# PiZero-RAK.net
KiCad netlist of a schematic drawn in EAGLE
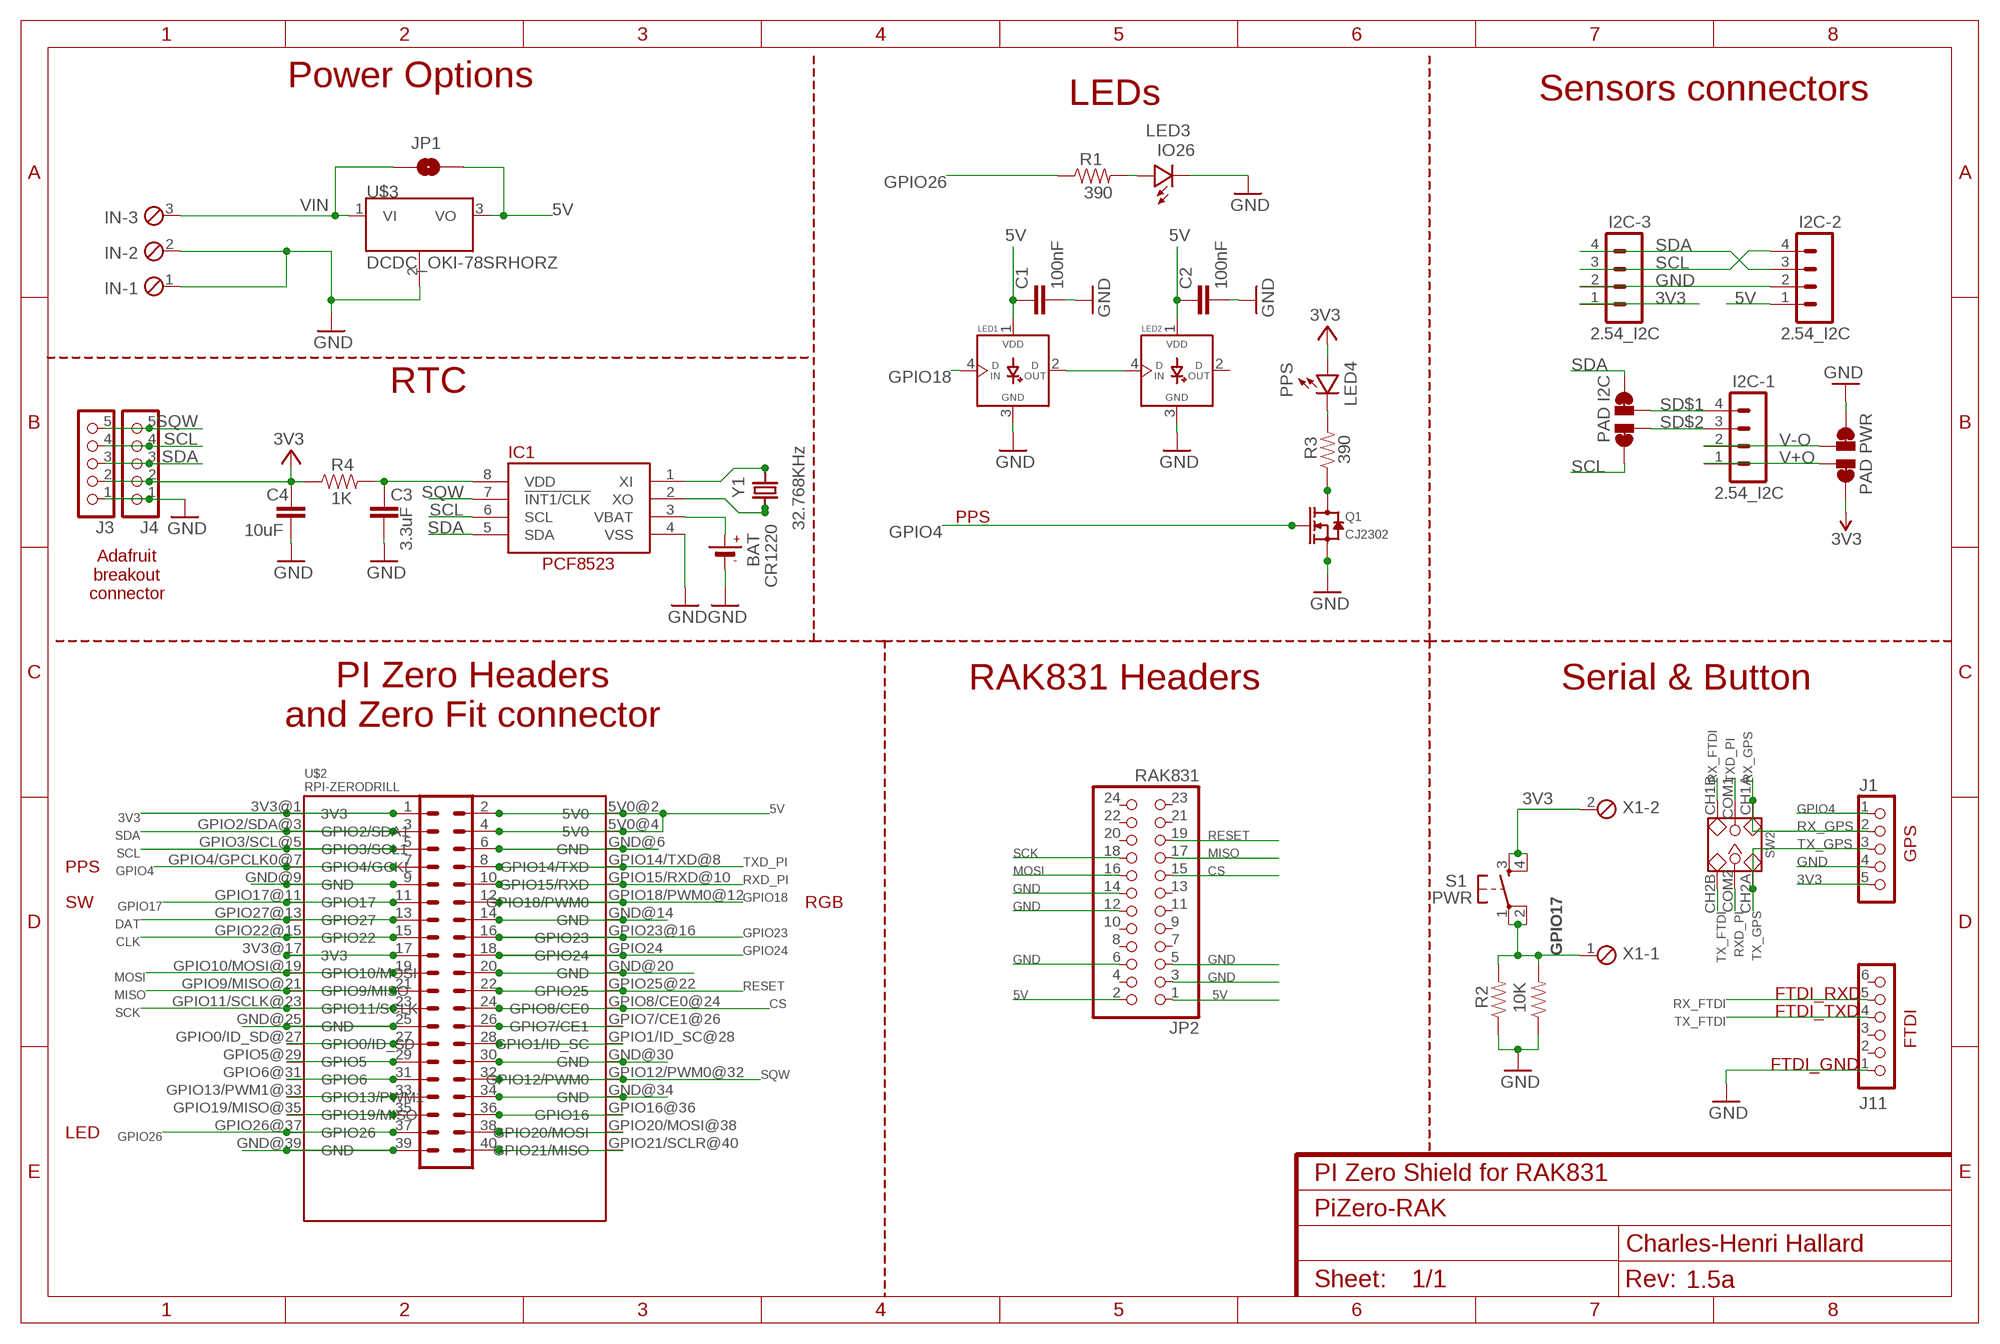
[diagram p0: schematic, sheet 1]

(export (version "E")
  (design (tool "Eeschema 10.0.6"))
  (components
    (comp (ref "BAT")
      (value "CR1220")
      (footprint "eagle-import:CR1220")
      (libsource (lib "eagle-import") (part "BATTERYCR1220_SMT"))
    )
    (comp (ref "C1")
      (value "100nF")
      (footprint "eagle-import:0805-CAP-LARGEPADS")
      (libsource (lib "eagle-import") (part "CAP0805-CAP-LARGEPADS"))
    )
    (comp (ref "C2")
      (value "100nF")
      (footprint "eagle-import:0805-CAP-LARGEPADS")
      (libsource (lib "eagle-import") (part "CAP0805-CAP-LARGEPADS"))
    )
    (comp (ref "C3")
      (value "3.3uF")
      (footprint "eagle-import:0805-CAP-LARGEPADS")
      (libsource (lib "eagle-import") (part "CAP0805-CAP-LARGEPADS"))
    )
    (comp (ref "C4")
      (value "10uF")
      (footprint "eagle-import:0805-CAP-LARGEPADS")
      (libsource (lib "eagle-import") (part "CAP0805-CAP-LARGEPADS"))
    )
    (comp (ref "I2C-1")
      (value "2.54_I2C")
      (footprint "eagle-import:1X04_NO_LOCK")
      (libsource (lib "eagle-import") (part "CON_HEADER_1X04'NO_LOCK'"))
    )
    (comp (ref "I2C-2")
      (value "2.54_I2C")
      (footprint "eagle-import:1X04_NO_LOCK")
      (libsource (lib "eagle-import") (part "CON_HEADER_1X04'NO_LOCK'"))
    )
    (comp (ref "I2C-3")
      (value "2.54_I2C")
      (footprint "eagle-import:1X04_NO_LOCK")
      (libsource (lib "eagle-import") (part "CON_HEADER_1X04'NO_LOCK'"))
    )
    (comp (ref "IC1")
      (value "PCF8523")
      (footprint "eagle-import:SOIC8_150MIL")
      (libsource (lib "eagle-import") (part "RTC_PCF8523T"))
    )
    (comp (ref "IN")
      (value "MPT3")
      (footprint "eagle-import:3POL254")
      (libsource (lib "eagle-import") (part "MPT3"))
    )
    (comp (ref "J1")
      (value "CON_HEADER_1X05-PTH")
      (footprint "eagle-import:M1X5")
      (libsource (lib "eagle-import") (part "CON_HEADER_1X05-PTH"))
    )
    (comp (ref "J2")
      (value "CONN_20X2HLE")
      (footprint "eagle-import:2X20-HLE")
      (libsource (lib "eagle-import") (part "CONN_20X2HLE"))
    )
    (comp (ref "J3")
      (value "CON_HEADER_1X05-PTH")
      (footprint "eagle-import:M1X5")
      (libsource (lib "eagle-import") (part "CON_HEADER_1X05-PTH"))
    )
    (comp (ref "J4")
      (value "CON_HEADER_1X05-PTH")
      (footprint "eagle-import:M1X5")
      (libsource (lib "eagle-import") (part "CON_HEADER_1X05-PTH"))
    )
    (comp (ref "J11")
      (value "CON_HEADER_1X06-PTH")
      (footprint "eagle-import:M1X6")
      (libsource (lib "eagle-import") (part "CON_HEADER_1X06-PTH"))
    )
    (comp (ref "JP1")
      (value "JUMPER-PAD-2-NOYES_SILK")
      (footprint "eagle-import:PAD-JUMPER-2-NO_YES_SILK")
      (libsource (lib "eagle-import") (part "JUMPER-PAD-2-NOYES_SILK"))
    )
    (comp (ref "JP2")
      (value "RAK831")
      (footprint "eagle-import:2X12")
      (libsource (lib "eagle-import") (part "PINHD-2X12"))
    )
    (comp (ref "LED1")
      (value "WS2812BLONG")
      (footprint "eagle-import:WS2812B-LONG")
      (libsource (lib "eagle-import") (part "WS2812BLONG"))
    )
    (comp (ref "LED2")
      (value "WS2812BLONG")
      (footprint "eagle-import:WS2812B-LONG")
      (libsource (lib "eagle-import") (part "WS2812BLONG"))
    )
    (comp (ref "LED3")
      (value "IO26")
      (footprint "eagle-import:0805-LED-LARGEPADS")
      (libsource (lib "eagle-import") (part "LED0805-LARGE"))
    )
    (comp (ref "LED4")
      (value "PPS")
      (footprint "eagle-import:0805-LED-LARGEPADS")
      (libsource (lib "eagle-import") (part "LED0805-LARGE"))
    )
    (comp (ref "Q1")
      (value "CJ2302")
      (footprint "eagle-import:SOT-23")
      (libsource (lib "eagle-import") (part "SMD-MOSFET-N-CH-20V-2.1A-CJ2302(SOT-23)"))
    )
    (comp (ref "R1")
      (value "390")
      (footprint "eagle-import:0805-RES")
      (libsource (lib "eagle-import") (part "RESISTOR0805-RES"))
    )
    (comp (ref "R2")
      (value "10K")
      (footprint "eagle-import:AXIAL-0.3")
      (libsource (lib "eagle-import") (part "RESISTORAXIAL-0.3"))
    )
    (comp (ref "R3")
      (value "390")
      (footprint "eagle-import:0805-RES")
      (libsource (lib "eagle-import") (part "RESISTOR0805-RES"))
    )
    (comp (ref "R4")
      (value "1K")
      (footprint "eagle-import:0805-RES")
      (libsource (lib "eagle-import") (part "RESISTOR0805-RES"))
    )
    (comp (ref "R105")
      (value "RESISTOR0805-RES")
      (footprint "eagle-import:0805-RES")
      (libsource (lib "eagle-import") (part "RESISTOR0805-RES"))
    )
    (comp (ref "S1")
      (value "PWR")
      (footprint "eagle-import:TAC-SWITCH-PTH")
      (libsource (lib "eagle-import") (part "TACTILE-SWITCH-PTH"))
    )
    (comp (ref "SW2")
      (value "DIP-TOGGLE-SWITCH-2CH-(2X3P-2.54)")
      (footprint "eagle-import:SW6-2.54-9.0X3.5X3.2+2.0MM")
      (fields (field (name "MPN") "MS-22D18 G2 ROHS"))
      (libsource (lib "eagle-import") (part "DIP-TOGGLE-SWITCH-2CH-(2X3P-2.54)"))
    )
    (comp (ref "U$2")
      (value "RPI-ZERODRILL")
      (footprint "eagle-import:RPI-ZERO-DRILLS")
      (libsource (lib "eagle-import") (part "RPI-ZERODRILL"))
    )
    (comp (ref "U$3")
      (value "DCDC_OKI-78SRHORZ")
      (footprint "eagle-import:OKI-78SRH")
      (libsource (lib "eagle-import") (part "DCDC_OKI-78SRHORZ"))
    )
    (comp (ref "U$4")
      (value "PAD PWR")
      (footprint "eagle-import:PAD-JUMPER-SWAP")
      (libsource (lib "eagle-import") (part "PAD-JUMPER-SWAPSWAP"))
    )
    (comp (ref "U$5")
      (value "PAD I2C")
      (footprint "eagle-import:PAD-JUMPER-SWAP")
      (libsource (lib "eagle-import") (part "PAD-JUMPER-SWAPSWAP"))
    )
    (comp (ref "X1")
      (value "MPT2")
      (footprint "eagle-import:2POL254")
      (libsource (lib "eagle-import") (part "MPT2"))
    )
    (comp (ref "Y1")
      (value "32.768KHz")
      (footprint "eagle-import:TC26H")
      (libsource (lib "eagle-import") (part "CRYSTALTC26H"))
    )
    (comp (ref "Y2")
      (value "CRYSTAL8X3.8SMT")
      (footprint "eagle-import:CRYSTAL_8X3.8")
      (libsource (lib "eagle-import") (part "CRYSTAL8X3.8SMT"))
    )
  )
  (nets
    (net (code "1") (name "/SD$1") (class "Default")
      (node (ref "I2C-1") (pin "4") (pinfunction "4_4") (pintype "passive"))
      (node (ref "U$5") (pin "3") (pinfunction "3_3") (pintype "passive"))
    )
    (net (code "2") (name "/SD$2") (class "Default")
      (node (ref "I2C-1") (pin "3") (pinfunction "3_3") (pintype "passive"))
      (node (ref "U$5") (pin "2") (pinfunction "2_2") (pintype "passive"))
    )
    (net (code "3") (name "/V+O") (class "Default")
      (node (ref "I2C-1") (pin "1") (pinfunction "1_1") (pintype "passive"))
      (node (ref "U$4") (pin "3") (pinfunction "3_3") (pintype "passive"))
    )
    (net (code "4") (name "/V-O") (class "Default")
      (node (ref "I2C-1") (pin "2") (pinfunction "2_2") (pintype "passive"))
      (node (ref "U$4") (pin "2") (pinfunction "2_2") (pintype "passive"))
    )
    (net (code "5") (name "/VIN") (class "Default")
      (node (ref "IN") (pin "3") (pinfunction "1_3") (pintype "passive"))
      (node (ref "JP1") (pin "1") (pinfunction "1_1") (pintype "passive"))
      (node (ref "U$3") (pin "1") (pinfunction "VI_1") (pintype "bidirectional"))
    )
    (net (code "6") (name "3V3") (class "Default")
      (node (ref "C4") (pin "1") (pinfunction "1_1") (pintype "passive"))
      (node (ref "I2C-3") (pin "1") (pinfunction "1_1") (pintype "passive"))
      (node (ref "J1") (pin "5") (pinfunction "5_5") (pintype "bidirectional"))
      (node (ref "J2") (pin "1") (pinfunction "1_1") (pintype "passive"))
      (node (ref "J3") (pin "2") (pinfunction "2_2") (pintype "bidirectional"))
      (node (ref "J4") (pin "2") (pinfunction "2_2") (pintype "bidirectional"))
      (node (ref "LED4") (pin "PLUS") (pinfunction "PLUS_PLUS") (pintype "passive"))
      (node (ref "R4") (pin "1") (pinfunction "1_1") (pintype "passive"))
      (node (ref "S1") (pin "3") (pinfunction "3_3") (pintype "passive"))
      (node (ref "S1") (pin "4") (pinfunction "4_4") (pintype "passive"))
      (node (ref "U$2") (pin "3V3@1") (pinfunction "3V3_3V3@1") (pintype "power_in"))
      (node (ref "U$4") (pin "4") (pinfunction "4_4") (pintype "passive"))
      (node (ref "U$4") (pin "44") (pinfunction "4_44") (pintype "passive"))
      (node (ref "X1") (pin "2") (pinfunction "1_2") (pintype "passive"))
    )
    (net (code "7") (name "5V") (class "Default")
      (node (ref "C1") (pin "1") (pinfunction "1_1") (pintype "passive"))
      (node (ref "C2") (pin "1") (pinfunction "1_1") (pintype "passive"))
      (node (ref "I2C-2") (pin "1") (pinfunction "1_1") (pintype "passive"))
      (node (ref "J2") (pin "2") (pinfunction "2_2") (pintype "passive"))
      (node (ref "J2") (pin "4") (pinfunction "4_4") (pintype "passive"))
      (node (ref "JP1") (pin "2") (pinfunction "2_2") (pintype "passive"))
      (node (ref "JP2") (pin "1") (pinfunction "1_1") (pintype "passive"))
      (node (ref "JP2") (pin "2") (pinfunction "2_2") (pintype "passive"))
      (node (ref "LED1") (pin "1") (pinfunction "VDD_1") (pintype "power_in"))
      (node (ref "LED2") (pin "1") (pinfunction "VDD_1") (pintype "power_in"))
      (node (ref "U$2") (pin "5V0@2") (pinfunction "5V0_5V0@2") (pintype "power_in"))
      (node (ref "U$2") (pin "5V0@4") (pinfunction "5V0_5V0@4") (pintype "power_in"))
      (node (ref "U$3") (pin "3") (pinfunction "VO_3") (pintype "bidirectional"))
    )
    (net (code "8") (name "CLK") (class "Default")
      (node (ref "J2") (pin "15") (pinfunction "15_15") (pintype "passive"))
      (node (ref "U$2") (pin "GPIO22@15") (pinfunction "GPIO22_GPIO22@15") (pintype "bidirectional"))
    )
    (net (code "9") (name "CS") (class "Default")
      (node (ref "J2") (pin "24") (pinfunction "24_24") (pintype "passive"))
      (node (ref "JP2") (pin "15") (pinfunction "15_15") (pintype "passive"))
      (node (ref "U$2") (pin "GPIO8/CE0@24") (pinfunction "GPIO8/CE0_GPIO8/CE0@24") (pintype "bidirectional"))
    )
    (net (code "10") (name "DAT") (class "Default")
      (node (ref "J2") (pin "13") (pinfunction "13_13") (pintype "passive"))
      (node (ref "U$2") (pin "GPIO27@13") (pinfunction "GPIO27_GPIO27@13") (pintype "bidirectional"))
    )
    (net (code "11") (name "GND") (class "Default")
      (node (ref "BAT") (pin "-") (pinfunction "-_-") (pintype "passive"))
      (node (ref "C1") (pin "2") (pinfunction "2_2") (pintype "passive"))
      (node (ref "C2") (pin "2") (pinfunction "2_2") (pintype "passive"))
      (node (ref "C3") (pin "2") (pinfunction "2_2") (pintype "passive"))
      (node (ref "C4") (pin "2") (pinfunction "2_2") (pintype "passive"))
      (node (ref "I2C-2") (pin "2") (pinfunction "2_2") (pintype "passive"))
      (node (ref "I2C-3") (pin "2") (pinfunction "2_2") (pintype "passive"))
      (node (ref "IC1") (pin "4") (pinfunction "VSS_4") (pintype "power_in"))
      (node (ref "IN") (pin "1") (pinfunction "1_1") (pintype "passive"))
      (node (ref "IN") (pin "2") (pinfunction "1_2") (pintype "passive"))
      (node (ref "J1") (pin "4") (pinfunction "4_4") (pintype "bidirectional"))
      (node (ref "J11") (pin "1") (pinfunction "1_1") (pintype "bidirectional"))
      (node (ref "J2") (pin "14") (pinfunction "14_14") (pintype "passive"))
      (node (ref "J2") (pin "20") (pinfunction "20_20") (pintype "passive"))
      (node (ref "J2") (pin "25") (pinfunction "25_25") (pintype "passive"))
      (node (ref "J2") (pin "30") (pinfunction "30_30") (pintype "passive"))
      (node (ref "J2") (pin "34") (pinfunction "34_34") (pintype "passive"))
      (node (ref "J2") (pin "39") (pinfunction "39_39") (pintype "passive"))
      (node (ref "J2") (pin "6") (pinfunction "6_6") (pintype "passive"))
      (node (ref "J2") (pin "9") (pinfunction "9_9") (pintype "passive"))
      (node (ref "J3") (pin "1") (pinfunction "1_1") (pintype "bidirectional"))
      (node (ref "J4") (pin "1") (pinfunction "1_1") (pintype "bidirectional"))
      (node (ref "JP2") (pin "12") (pinfunction "12_12") (pintype "passive"))
      (node (ref "JP2") (pin "14") (pinfunction "14_14") (pintype "passive"))
      (node (ref "JP2") (pin "3") (pinfunction "3_3") (pintype "passive"))
      (node (ref "JP2") (pin "5") (pinfunction "5_5") (pintype "passive"))
      (node (ref "JP2") (pin "6") (pinfunction "6_6") (pintype "passive"))
      (node (ref "LED1") (pin "3") (pinfunction "GND_3") (pintype "power_in"))
      (node (ref "LED2") (pin "3") (pinfunction "GND_3") (pintype "power_in"))
      (node (ref "LED3") (pin "MINUS") (pinfunction "MINUS_MINUS") (pintype "passive"))
      (node (ref "Q1") (pin "2") (pinfunction "S_2") (pintype "passive"))
      (node (ref "R105") (pin "1") (pinfunction "1_1") (pintype "passive"))
      (node (ref "R2") (pin "P$1") (pinfunction "1_P$1") (pintype "passive"))
      (node (ref "U$2") (pin "GND@14") (pinfunction "GND_GND@14") (pintype "power_in"))
      (node (ref "U$2") (pin "GND@20") (pinfunction "GND_GND@20") (pintype "power_in"))
      (node (ref "U$2") (pin "GND@25") (pinfunction "GND_GND@25") (pintype "power_in"))
      (node (ref "U$2") (pin "GND@30") (pinfunction "GND_GND@30") (pintype "power_in"))
      (node (ref "U$2") (pin "GND@34") (pinfunction "GND_GND@34") (pintype "power_in"))
      (node (ref "U$2") (pin "GND@39") (pinfunction "GND_GND@39") (pintype "power_in"))
      (node (ref "U$2") (pin "GND@6") (pinfunction "GND_GND@6") (pintype "power_in"))
      (node (ref "U$2") (pin "GND@9") (pinfunction "GND_GND@9") (pintype "power_in"))
      (node (ref "U$3") (pin "2") (pinfunction "GND_2") (pintype "bidirectional"))
      (node (ref "U$4") (pin "1") (pinfunction "1_1") (pintype "passive"))
      (node (ref "U$4") (pin "11") (pinfunction "1_11") (pintype "passive"))
    )
    (net (code "12") (name "GPIO4") (class "Default")
      (node (ref "J1") (pin "1") (pinfunction "1_1") (pintype "bidirectional"))
      (node (ref "J2") (pin "7") (pinfunction "7_7") (pintype "passive"))
      (node (ref "Q1") (pin "1") (pinfunction "G_1") (pintype "passive"))
      (node (ref "U$2") (pin "GPIO4/GPCLK0@7") (pinfunction "GPIO4/GCKL_GPIO4/GPCLK0@7") (pintype "bidirectional"))
    )
    (net (code "13") (name "GPIO17") (class "Default")
      (node (ref "J2") (pin "11") (pinfunction "11_11") (pintype "passive"))
      (node (ref "R105") (pin "2") (pinfunction "2_2") (pintype "passive"))
      (node (ref "R2") (pin "P$2") (pinfunction "2_P$2") (pintype "passive"))
      (node (ref "S1") (pin "1") (pinfunction "1_1") (pintype "passive"))
      (node (ref "S1") (pin "2") (pinfunction "2_2") (pintype "passive"))
      (node (ref "U$2") (pin "GPIO17@11") (pinfunction "GPIO17_GPIO17@11") (pintype "bidirectional"))
      (node (ref "X1") (pin "1") (pinfunction "1_1") (pintype "passive"))
    )
    (net (code "14") (name "GPIO18") (class "Default")
      (node (ref "J2") (pin "12") (pinfunction "12_12") (pintype "passive"))
      (node (ref "LED1") (pin "4") (pinfunction "DIN_4") (pintype "input"))
      (node (ref "U$2") (pin "GPIO18/PWM0@12") (pinfunction "GPIO18/PWM0_GPIO18/PWM0@12") (pintype "bidirectional"))
    )
    (net (code "15") (name "GPIO23") (class "Default")
      (node (ref "J2") (pin "16") (pinfunction "16_16") (pintype "passive"))
      (node (ref "U$2") (pin "GPIO23@16") (pinfunction "GPIO23_GPIO23@16") (pintype "bidirectional"))
    )
    (net (code "16") (name "GPIO24") (class "Default")
      (node (ref "J2") (pin "18") (pinfunction "18_18") (pintype "passive"))
      (node (ref "U$2") (pin "GPIO24") (pinfunction "GPIO24_GPIO24") (pintype "bidirectional"))
    )
    (net (code "17") (name "GPIO26") (class "Default")
      (node (ref "J2") (pin "37") (pinfunction "37_37") (pintype "passive"))
      (node (ref "R1") (pin "1") (pinfunction "1_1") (pintype "passive"))
      (node (ref "U$2") (pin "GPIO26@37") (pinfunction "GPIO26_GPIO26@37") (pintype "bidirectional"))
    )
    (net (code "18") (name "MISO") (class "Default")
      (node (ref "J2") (pin "21") (pinfunction "21_21") (pintype "passive"))
      (node (ref "JP2") (pin "17") (pinfunction "17_17") (pintype "passive"))
      (node (ref "U$2") (pin "GPIO9/MISO@21") (pinfunction "GPIO9/MISO_GPIO9/MISO@21") (pintype "bidirectional"))
    )
    (net (code "19") (name "MOSI") (class "Default")
      (node (ref "J2") (pin "19") (pinfunction "19_19") (pintype "passive"))
      (node (ref "JP2") (pin "16") (pinfunction "16_16") (pintype "passive"))
      (node (ref "U$2") (pin "GPIO10/MOSI@19") (pinfunction "GPIO10/MOSI_GPIO10/MOSI@19") (pintype "bidirectional"))
    )
    (net (code "20") (name "Net-(BAT-+)") (class "Default")
      (node (ref "BAT") (pin "+$1") (pinfunction "+_+$1") (pintype "passive"))
      (node (ref "IC1") (pin "3") (pinfunction "VBAT_3") (pintype "power_in"))
    )
    (net (code "21") (name "Net-(IC1-VDD)") (class "Default")
      (node (ref "C3") (pin "1") (pinfunction "1_1") (pintype "passive"))
      (node (ref "IC1") (pin "8") (pinfunction "VDD_8") (pintype "power_in"))
      (node (ref "R4") (pin "2") (pinfunction "2_2") (pintype "passive"))
    )
    (net (code "22") (name "Net-(IC1-XI)") (class "Default")
      (node (ref "IC1") (pin "1") (pinfunction "XI_1") (pintype "input"))
      (node (ref "Y1") (pin "1") (pinfunction "1_1") (pintype "passive"))
      (node (ref "Y2") (pin "P$4") (pinfunction "2_P$4") (pintype "passive"))
    )
    (net (code "23") (name "Net-(IC1-XO)") (class "Default")
      (node (ref "IC1") (pin "2") (pinfunction "XO_2") (pintype "output"))
      (node (ref "Y1") (pin "2") (pinfunction "2_2") (pintype "passive"))
      (node (ref "Y2") (pin "P$1") (pinfunction "1_P$1") (pintype "passive"))
    )
    (net (code "24") (name "Net-(J2-Pad17)") (class "Default")
      (node (ref "J2") (pin "17") (pinfunction "17_17") (pintype "passive"))
      (node (ref "U$2") (pin "3V3@17") (pinfunction "3V3_3V3@17") (pintype "power_in"))
    )
    (net (code "25") (name "Net-(LED1-DOUT)") (class "Default")
      (node (ref "LED1") (pin "2") (pinfunction "DOUT_2") (pintype "output"))
      (node (ref "LED2") (pin "4") (pinfunction "DIN_4") (pintype "input"))
    )
    (net (code "26") (name "Net-(LED3-PadPLUS)") (class "Default")
      (node (ref "LED3") (pin "PLUS") (pinfunction "PLUS_PLUS") (pintype "passive"))
      (node (ref "R1") (pin "2") (pinfunction "2_2") (pintype "passive"))
    )
    (net (code "27") (name "Net-(LED4-PadMINUS)") (class "Default")
      (node (ref "LED4") (pin "MINUS") (pinfunction "MINUS_MINUS") (pintype "passive"))
      (node (ref "R3") (pin "2") (pinfunction "2_2") (pintype "passive"))
    )
    (net (code "28") (name "Net-(Q1-D)") (class "Default")
      (node (ref "Q1") (pin "3") (pinfunction "D_3") (pintype "passive"))
      (node (ref "R3") (pin "1") (pinfunction "1_1") (pintype "passive"))
    )
    (net (code "29") (name "Net-(U$2-GPIO0{slash}ID_SD)") (class "Default")
      (node (ref "J2") (pin "27") (pinfunction "27_27") (pintype "passive"))
      (node (ref "U$2") (pin "GPIO0/ID_SD@27") (pinfunction "GPIO0/ID_SD_GPIO0/ID_SD@27") (pintype "bidirectional"))
    )
    (net (code "30") (name "Net-(U$2-GPIO1{slash}ID_SC)") (class "Default")
      (node (ref "J2") (pin "28") (pinfunction "28_28") (pintype "passive"))
      (node (ref "U$2") (pin "GPIO1/ID_SC@28") (pinfunction "GPIO1/ID_SC_GPIO1/ID_SC@28") (pintype "bidirectional"))
    )
    (net (code "31") (name "Net-(U$2-GPIO5)") (class "Default")
      (node (ref "J2") (pin "29") (pinfunction "29_29") (pintype "passive"))
      (node (ref "U$2") (pin "GPIO5@29") (pinfunction "GPIO5_GPIO5@29") (pintype "bidirectional"))
    )
    (net (code "32") (name "Net-(U$2-GPIO6)") (class "Default")
      (node (ref "J2") (pin "31") (pinfunction "31_31") (pintype "passive"))
      (node (ref "U$2") (pin "GPIO6@31") (pinfunction "GPIO6_GPIO6@31") (pintype "bidirectional"))
    )
    (net (code "33") (name "Net-(U$2-GPIO7{slash}CE1)") (class "Default")
      (node (ref "J2") (pin "26") (pinfunction "26_26") (pintype "passive"))
      (node (ref "U$2") (pin "GPIO7/CE1@26") (pinfunction "GPIO7/CE1_GPIO7/CE1@26") (pintype "bidirectional"))
    )
    (net (code "34") (name "Net-(U$2-GPIO13{slash}PWM1)") (class "Default")
      (node (ref "J2") (pin "33") (pinfunction "33_33") (pintype "passive"))
      (node (ref "U$2") (pin "GPIO13/PWM1@33") (pinfunction "GPIO13/PWM1_GPIO13/PWM1@33") (pintype "bidirectional"))
    )
    (net (code "35") (name "Net-(U$2-GPIO16)") (class "Default")
      (node (ref "J2") (pin "36") (pinfunction "36_36") (pintype "passive"))
      (node (ref "U$2") (pin "GPIO16@36") (pinfunction "GPIO16_GPIO16@36") (pintype "bidirectional"))
    )
    (net (code "36") (name "Net-(U$2-GPIO19{slash}MISO)") (class "Default")
      (node (ref "J2") (pin "35") (pinfunction "35_35") (pintype "passive"))
      (node (ref "U$2") (pin "GPIO19/MISO@35") (pinfunction "GPIO19/MISO_GPIO19/MISO@35") (pintype "bidirectional"))
    )
    (net (code "37") (name "Net-(U$2-GPIO20{slash}MOSI)") (class "Default")
      (node (ref "J2") (pin "38") (pinfunction "38_38") (pintype "passive"))
      (node (ref "U$2") (pin "GPIO20/MOSI@38") (pinfunction "GPIO20/MOSI_GPIO20/MOSI@38") (pintype "bidirectional"))
    )
    (net (code "38") (name "Net-(U$2-GPIO21{slash}MISO)") (class "Default")
      (node (ref "J2") (pin "40") (pinfunction "40_40") (pintype "passive"))
      (node (ref "U$2") (pin "GPIO21/SCLR@40") (pinfunction "GPIO21/MISO_GPIO21/SCLR@40") (pintype "bidirectional"))
    )
    (net (code "39") (name "RESET") (class "Default")
      (node (ref "J2") (pin "22") (pinfunction "22_22") (pintype "passive"))
      (node (ref "JP2") (pin "19") (pinfunction "19_19") (pintype "passive"))
      (node (ref "U$2") (pin "GPIO25@22") (pinfunction "GPIO25_GPIO25@22") (pintype "bidirectional"))
    )
    (net (code "40") (name "RXD_PI") (class "Default")
      (node (ref "J2") (pin "10") (pinfunction "10_10") (pintype "passive"))
      (node (ref "SW2") (pin "COM2") (pinfunction "COM2_COM2") (pintype "bidirectional"))
      (node (ref "U$2") (pin "GPIO15/RXD@10") (pinfunction "GPIO15/RXD_GPIO15/RXD@10") (pintype "bidirectional"))
    )
    (net (code "41") (name "RX_FTDI") (class "Default")
      (node (ref "J11") (pin "5") (pinfunction "5_5") (pintype "passive"))
      (node (ref "SW2") (pin "CH1B") (pinfunction "CH1B_CH1B") (pintype "bidirectional"))
    )
    (net (code "42") (name "RX_GPS") (class "Default")
      (node (ref "J1") (pin "2") (pinfunction "2_2") (pintype "bidirectional"))
      (node (ref "SW2") (pin "CH1A") (pinfunction "CH1A_CH1A") (pintype "bidirectional"))
    )
    (net (code "43") (name "SCK") (class "Default")
      (node (ref "J2") (pin "23") (pinfunction "23_23") (pintype "passive"))
      (node (ref "JP2") (pin "18") (pinfunction "18_18") (pintype "passive"))
      (node (ref "U$2") (pin "GPIO11/SCLK@23") (pinfunction "GPIO11/SCLK_GPIO11/SCLK@23") (pintype "bidirectional"))
    )
    (net (code "44") (name "SCL") (class "Default")
      (node (ref "I2C-2") (pin "4") (pinfunction "4_4") (pintype "passive"))
      (node (ref "I2C-3") (pin "3") (pinfunction "3_3") (pintype "passive"))
      (node (ref "IC1") (pin "6") (pinfunction "SCL_6") (pintype "bidirectional"))
      (node (ref "J2") (pin "5") (pinfunction "5_5") (pintype "passive"))
      (node (ref "J3") (pin "4") (pinfunction "4_4") (pintype "bidirectional"))
      (node (ref "J4") (pin "4") (pinfunction "4_4") (pintype "bidirectional"))
      (node (ref "U$2") (pin "GPIO3/SCL@5") (pinfunction "GPIO3/SCL1_GPIO3/SCL@5") (pintype "bidirectional"))
      (node (ref "U$5") (pin "1") (pinfunction "1_1") (pintype "passive"))
      (node (ref "U$5") (pin "11") (pinfunction "1_11") (pintype "passive"))
    )
    (net (code "45") (name "SDA") (class "Default")
      (node (ref "I2C-2") (pin "3") (pinfunction "3_3") (pintype "passive"))
      (node (ref "I2C-3") (pin "4") (pinfunction "4_4") (pintype "passive"))
      (node (ref "IC1") (pin "5") (pinfunction "SDA_5") (pintype "bidirectional"))
      (node (ref "J2") (pin "3") (pinfunction "3_3") (pintype "passive"))
      (node (ref "J3") (pin "3") (pinfunction "3_3") (pintype "bidirectional"))
      (node (ref "J4") (pin "3") (pinfunction "3_3") (pintype "bidirectional"))
      (node (ref "U$2") (pin "GPIO2/SDA@3") (pinfunction "GPIO2/SDA1_GPIO2/SDA@3") (pintype "bidirectional"))
      (node (ref "U$5") (pin "4") (pinfunction "4_4") (pintype "passive"))
      (node (ref "U$5") (pin "44") (pinfunction "4_44") (pintype "passive"))
    )
    (net (code "46") (name "SQW") (class "Default")
      (node (ref "IC1") (pin "7") (pinfunction "~{INT1/CLK}_7") (pintype "output"))
      (node (ref "J2") (pin "32") (pinfunction "32_32") (pintype "passive"))
      (node (ref "J3") (pin "5") (pinfunction "5_5") (pintype "bidirectional"))
      (node (ref "J4") (pin "5") (pinfunction "5_5") (pintype "bidirectional"))
      (node (ref "U$2") (pin "GPIO12/PWM0@32") (pinfunction "GPIO12/PWM0_GPIO12/PWM0@32") (pintype "bidirectional"))
    )
    (net (code "47") (name "TXD_PI") (class "Default")
      (node (ref "J2") (pin "8") (pinfunction "8_8") (pintype "passive"))
      (node (ref "SW2") (pin "COM1") (pinfunction "COM1_COM1") (pintype "bidirectional"))
      (node (ref "U$2") (pin "GPIO14/TXD@8") (pinfunction "GPIO14/TXD_GPIO14/TXD@8") (pintype "bidirectional"))
    )
    (net (code "48") (name "TX_FTDI") (class "Default")
      (node (ref "J11") (pin "4") (pinfunction "4_4") (pintype "passive"))
      (node (ref "SW2") (pin "CH2B") (pinfunction "CH2B_CH2B") (pintype "bidirectional"))
    )
    (net (code "49") (name "TX_GPS") (class "Default")
      (node (ref "J1") (pin "3") (pinfunction "3_3") (pintype "bidirectional"))
      (node (ref "SW2") (pin "CH2A") (pinfunction "CH2A_CH2A") (pintype "bidirectional"))
    )
    (net (code "50") (name "unconnected-(J11-Pad2)") (class "Default")
      (node (ref "J11") (pin "2") (pinfunction "2_2") (pintype "bidirectional"))
    )
    (net (code "51") (name "unconnected-(J11-Pad3)") (class "Default")
      (node (ref "J11") (pin "3") (pinfunction "3_3") (pintype "passive"))
    )
    (net (code "52") (name "unconnected-(J11-Pad6)") (class "Default")
      (node (ref "J11") (pin "6") (pinfunction "6_6") (pintype "passive"))
    )
    (net (code "53") (name "unconnected-(JP2-Pad4)") (class "Default")
      (node (ref "JP2") (pin "4") (pinfunction "4_4") (pintype "passive"))
    )
    (net (code "54") (name "unconnected-(JP2-Pad7)") (class "Default")
      (node (ref "JP2") (pin "7") (pinfunction "7_7") (pintype "passive"))
    )
    (net (code "55") (name "unconnected-(JP2-Pad8)") (class "Default")
      (node (ref "JP2") (pin "8") (pinfunction "8_8") (pintype "passive"))
    )
    (net (code "56") (name "unconnected-(JP2-Pad9)") (class "Default")
      (node (ref "JP2") (pin "9") (pinfunction "9_9") (pintype "passive"))
    )
    (net (code "57") (name "unconnected-(JP2-Pad10)") (class "Default")
      (node (ref "JP2") (pin "10") (pinfunction "10_10") (pintype "passive"))
    )
    (net (code "58") (name "unconnected-(JP2-Pad11)") (class "Default")
      (node (ref "JP2") (pin "11") (pinfunction "11_11") (pintype "passive"))
    )
    (net (code "59") (name "unconnected-(JP2-Pad13)") (class "Default")
      (node (ref "JP2") (pin "13") (pinfunction "13_13") (pintype "passive"))
    )
    (net (code "60") (name "unconnected-(JP2-Pad20)") (class "Default")
      (node (ref "JP2") (pin "20") (pinfunction "20_20") (pintype "passive"))
    )
    (net (code "61") (name "unconnected-(JP2-Pad21)") (class "Default")
      (node (ref "JP2") (pin "21") (pinfunction "21_21") (pintype "passive"))
    )
    (net (code "62") (name "unconnected-(JP2-Pad22)") (class "Default")
      (node (ref "JP2") (pin "22") (pinfunction "22_22") (pintype "passive"))
    )
    (net (code "63") (name "unconnected-(JP2-Pad23)") (class "Default")
      (node (ref "JP2") (pin "23") (pinfunction "23_23") (pintype "passive"))
    )
    (net (code "64") (name "unconnected-(JP2-Pad24)") (class "Default")
      (node (ref "JP2") (pin "24") (pinfunction "24_24") (pintype "passive"))
    )
    (net (code "65") (name "unconnected-(LED2-DOUT-Pad2)") (class "Default")
      (node (ref "LED2") (pin "2") (pinfunction "DOUT_2") (pintype "output"))
    )
  )
)
